# HP_LASER_PS.net
KiCad netlist of a schematic drawn in Altium Designer
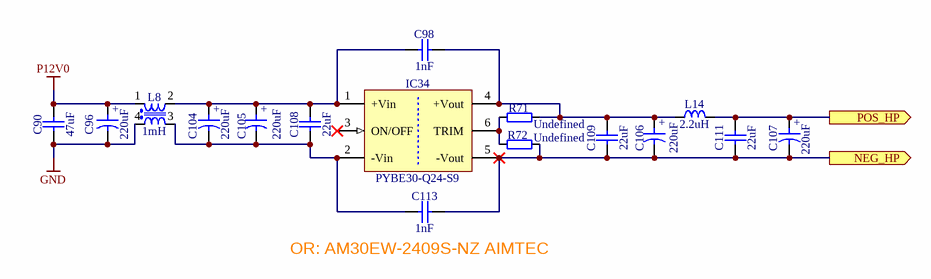
[diagram p0: HP_LASER_PS.SchDoc]

(export (version "E")
  (design (tool "Eeschema 10.0.6"))
  (components
    (comp (ref "C90")
      (value "47uF")
      (footprint "CAPC3225X270N")
      (description "Non-polarised capacitor")
      (fields
        (field (name "PART NUMBER") "CC1210_47UF_16V_20%_X5R")
        (field (name "VOLTAGE") "16V")
        (field (name "AUTHOR") "CERN DEM MR")
      )
      (libsource (lib "Capacitors") (part "Capacitor - non polarized"))
    )
    (comp (ref "C96")
      (value "220uF")
      (footprint "CAPAE830X1020N")
      (description "Polarised capacitor")
      (fields
        (field (name "PART NUMBER") "CAE830-1020_220UF_25V_20%")
        (field (name "VOLTAGE") "25V")
        (field (name "AUTHOR") "CERN DEM JLC")
      )
      (libsource (lib "Capacitors") (part "Capacitor - polarized"))
    )
    (comp (ref "C98")
      (value "1nF")
      (footprint "CAPC3216X180N")
      (description "Non-polarised capacitor")
      (fields
        (field (name "PART NUMBER") "CC1206_1NF_2KV_10%_X7R")
        (field (name "VOLTAGE") "2kV")
        (field (name "AUTHOR") "CERN DEM JLC")
      )
      (libsource (lib "Capacitors") (part "Capacitor - non polarized"))
    )
    (comp (ref "C104")
      (value "220uF")
      (footprint "CAPAE830X1020N")
      (description "Polarised capacitor")
      (fields
        (field (name "PART NUMBER") "CAE830-1020_220UF_25V_20%")
        (field (name "VOLTAGE") "25V")
        (field (name "AUTHOR") "CERN DEM JLC")
      )
      (libsource (lib "Capacitors") (part "Capacitor - polarized"))
    )
    (comp (ref "C105")
      (value "220uF")
      (footprint "CAPAE830X1020N")
      (description "Polarised capacitor")
      (fields
        (field (name "PART NUMBER") "CAE830-1020_220UF_25V_20%")
        (field (name "VOLTAGE") "25V")
        (field (name "AUTHOR") "CERN DEM JLC")
      )
      (libsource (lib "Capacitors") (part "Capacitor - polarized"))
    )
    (comp (ref "C106")
      (value "220uF")
      (footprint "CAPAE830X1020N")
      (description "Polarised capacitor")
      (fields
        (field (name "PART NUMBER") "CAE830-1020_220UF_25V_20%")
        (field (name "VOLTAGE") "25V")
        (field (name "AUTHOR") "CERN DEM JLC")
      )
      (libsource (lib "Capacitors") (part "Capacitor - polarized"))
    )
    (comp (ref "C107")
      (value "220uF")
      (footprint "CAPAE830X1020N")
      (description "Polarised capacitor")
      (fields
        (field (name "PART NUMBER") "CAE830-1020_220UF_25V_20%")
        (field (name "VOLTAGE") "25V")
        (field (name "AUTHOR") "CERN DEM JLC")
      )
      (libsource (lib "Capacitors") (part "Capacitor - polarized"))
    )
    (comp (ref "C108")
      (value "22uF")
      (footprint "CAPC3216X180N")
      (description "Non-polarised capacitor")
      (fields
        (field (name "PART NUMBER") "CC1206_22UF_35V_20%_JB_TDK_C3216JB1V226M160AC")
        (field (name "VOLTAGE") "35V")
        (field (name "AUTHOR") "CERN DEM JLC")
      )
      (libsource (lib "Capacitors") (part "Capacitor - non polarized"))
    )
    (comp (ref "C109")
      (value "22uF")
      (footprint "CAPC3216X180N")
      (description "Non-polarised capacitor")
      (fields
        (field (name "PART NUMBER") "CC1206_22UF_35V_20%_JB_TDK_C3216JB1V226M160AC")
        (field (name "VOLTAGE") "35V")
        (field (name "AUTHOR") "CERN DEM JLC")
      )
      (libsource (lib "Capacitors") (part "Capacitor - non polarized"))
    )
    (comp (ref "C111")
      (value "22uF")
      (footprint "CAPC3216X180N")
      (description "Non-polarised capacitor")
      (fields
        (field (name "PART NUMBER") "CC1206_22UF_35V_20%_JB_TDK_C3216JB1V226M160AC")
        (field (name "VOLTAGE") "35V")
        (field (name "AUTHOR") "CERN DEM JLC")
      )
      (libsource (lib "Capacitors") (part "Capacitor - non polarized"))
    )
    (comp (ref "C113")
      (value "1nF")
      (footprint "CAPC3216X180N")
      (description "Non-polarised capacitor")
      (fields
        (field (name "PART NUMBER") "CC1206_1NF_2KV_10%_X7R")
        (field (name "VOLTAGE") "2kV")
        (field (name "AUTHOR") "CERN DEM JLC")
      )
      (libsource (lib "Capacitors") (part "Capacitor - non polarized"))
    )
    (comp (ref "IC34")
      (value "PYBE30-Q24-S9")
      (footprint "DCDC_TRACO_TEN30")
      (description "TRACO, TEN30 Series, Single Output DCDC Converter")
      (fields (field (name "MANUFACTURER") "CUI") (field (name "AUTHOR") "CERN DEM JMW"))
      (libsource (lib "ICs And Semiconductors") (part "DCDC_TRACO_TEN30_Single Output"))
    )
    (comp (ref "L8")
      (value "1mH")
      (footprint "IND_WURTH_WE-CMB-XS")
      (description "Inductor Common Mode")
      (fields
        (field (name "PART NUMBER") "IND_1MH_30%_WURTH_WE-CMB-XS")
        (field (name "POWER") "2A")
        (field (name "AUTHOR") "CERN DEM JLC")
      )
      (libsource (lib "Inductors & Transformers") (part "Inductor Common Mode 1Dot-2 4Dot-3"))
    )
    (comp (ref "L14")
      (value "2.2uH")
      (footprint "IND_BOURNS_SRR1260")
      (description "Inductor")
      (fields
        (field (name "PART NUMBER") "IND_2.2UH_30%_BOURNS_SRR1260")
        (field (name "POWER") "8.2A")
        (field (name "AUTHOR") "CERN DEM JLC")
      )
      (libsource (lib "Inductors & Transformers") (part "Inductor"))
    )
    (comp (ref "R71")
      (value "Undefined")
      (footprint "RESC1608X55N")
      (description "Resistor")
      (fields (field (name "PART NUMBER") "R0603_NO-VALUE") (field (name "AUTHOR") "CERN DEM JLC"))
      (libsource (lib "Resistors") (part "Resistor"))
    )
    (comp (ref "R72")
      (value "Undefined")
      (footprint "RESC1608X55N")
      (description "Resistor")
      (fields (field (name "PART NUMBER") "R0603_NO-VALUE") (field (name "AUTHOR") "CERN DEM JLC"))
      (libsource (lib "Resistors") (part "Resistor"))
    )
  )
  (nets
    (net (code "1") (name "/NEG_HP") (class "Default")
      (node (ref "C106") (pin "2") (pinfunction "2_2") (pintype "passive"))
      (node (ref "C107") (pin "2") (pinfunction "2_2") (pintype "passive"))
      (node (ref "C109") (pin "1") (pinfunction "1_1") (pintype "passive"))
      (node (ref "C111") (pin "1") (pinfunction "1_1") (pintype "passive"))
      (node (ref "C113") (pin "2") (pinfunction "2_2") (pintype "passive"))
      (node (ref "IC34") (pin "5") (pinfunction "-Vout_5") (pintype "power_in"))
      (node (ref "R72") (pin "1") (pinfunction "1_1") (pintype "passive"))
    )
    (net (code "2") (name "/POS_HP") (class "Default")
      (node (ref "C107") (pin "1") (pinfunction "1_1") (pintype "passive"))
      (node (ref "C111") (pin "2") (pinfunction "2_2") (pintype "passive"))
      (node (ref "L14") (pin "2") (pinfunction "2_2") (pintype "passive"))
    )
    (net (code "3") (name "GND") (class "Default")
      (node (ref "C90") (pin "1") (pinfunction "1_1") (pintype "passive"))
      (node (ref "C96") (pin "2") (pinfunction "2_2") (pintype "passive"))
      (node (ref "L8") (pin "4") (pinfunction "4_4") (pintype "passive"))
    )
    (net (code "4") (name "Net-(IC34-+Vin)") (class "Default")
      (node (ref "C104") (pin "1") (pinfunction "1_1") (pintype "passive"))
      (node (ref "C105") (pin "1") (pinfunction "1_1") (pintype "passive"))
      (node (ref "C108") (pin "2") (pinfunction "2_2") (pintype "passive"))
      (node (ref "C98") (pin "1") (pinfunction "1_1") (pintype "passive"))
      (node (ref "IC34") (pin "1") (pinfunction "+Vin_1") (pintype "power_in"))
      (node (ref "L8") (pin "2") (pinfunction "2_2") (pintype "passive"))
    )
    (net (code "5") (name "Net-(IC34-+Vout)") (class "Default")
      (node (ref "C106") (pin "1") (pinfunction "1_1") (pintype "passive"))
      (node (ref "C109") (pin "2") (pinfunction "2_2") (pintype "passive"))
      (node (ref "C98") (pin "2") (pinfunction "2_2") (pintype "passive"))
      (node (ref "IC34") (pin "4") (pinfunction "+Vout_4") (pintype "power_in"))
      (node (ref "L14") (pin "1") (pinfunction "1_1") (pintype "passive"))
      (node (ref "R71") (pin "1") (pinfunction "1_1") (pintype "passive"))
    )
    (net (code "6") (name "Net-(IC34--Vin)") (class "Default")
      (node (ref "C104") (pin "2") (pinfunction "2_2") (pintype "passive"))
      (node (ref "C105") (pin "2") (pinfunction "2_2") (pintype "passive"))
      (node (ref "C108") (pin "1") (pinfunction "1_1") (pintype "passive"))
      (node (ref "C113") (pin "1") (pinfunction "1_1") (pintype "passive"))
      (node (ref "IC34") (pin "2") (pinfunction "-Vin_2") (pintype "power_in"))
      (node (ref "L8") (pin "3") (pinfunction "3_3") (pintype "passive"))
    )
    (net (code "7") (name "Net-(IC34-TRIM)") (class "Default")
      (node (ref "IC34") (pin "6") (pinfunction "TRIM_6") (pintype "power_in"))
      (node (ref "R71") (pin "2") (pinfunction "2_2") (pintype "passive"))
      (node (ref "R72") (pin "2") (pinfunction "2_2") (pintype "passive"))
    )
    (net (code "8") (name "P12V0") (class "Default")
      (node (ref "C90") (pin "2") (pinfunction "2_2") (pintype "passive"))
      (node (ref "C96") (pin "1") (pinfunction "1_1") (pintype "passive"))
      (node (ref "L8") (pin "1") (pinfunction "1_1") (pintype "passive"))
    )
    (net (code "9") (name "unconnected-(IC34-ON{slash}OFF-Pad3)") (class "Default")
      (node (ref "IC34") (pin "3") (pinfunction "ON/OFF_3") (pintype "input+no_connect"))
    )
  )
)
